# Isolation.net
KiCad netlist of a schematic drawn in Altium Designer
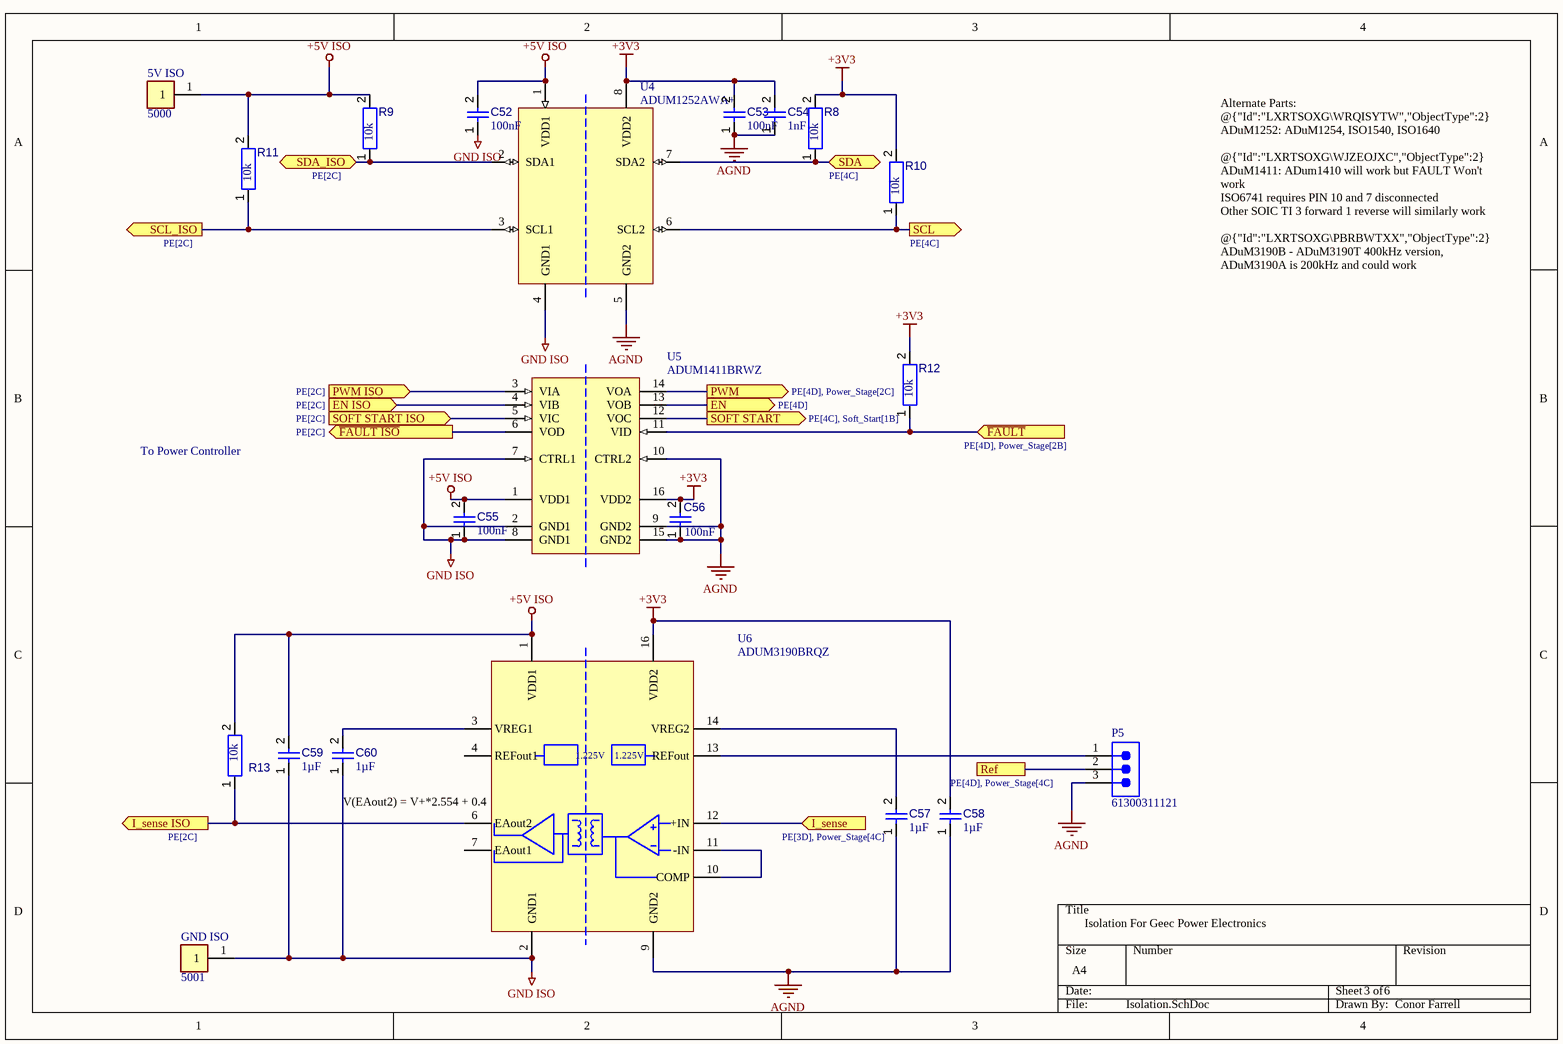
[diagram p0: Isolation.SchDoc]

(export (version "E")
  (design (tool "Eeschema 10.0.6"))
  (components
    (comp (ref "5V ISO")
      (value "5000")
      (footprint "FP-5000-MFG")
      (description "Cable Wrap, 1/2 Inch, Polyethylene, Natural, 50 Ft, Spirap Series")
      (libsource (lib "University of Galway") (part "1e4615820a309e3ce90f9e6d957b7fa"))
    )
    (comp (ref "C52")
      (value "100nF")
      (footprint "CAPC3216X06N")
      (description "Ceramic Capacitor, Multilayer, Ceramic, 200V, 10% +Tol, 10% -Tol, X7R, 15% TC, 0.01uF, 1206")
      (fields (field (name "TOLERANCE") "10%") (field (name "Comment") "C1206C104K1RACTU"))
      (libsource (lib "University of Galway") (part "CAP-NP-2"))
    )
    (comp (ref "C53")
      (value "100nF")
      (footprint "CAPC3216X06N")
      (description "Ceramic Capacitor, Multilayer, Ceramic, 200V, 10% +Tol, 10% -Tol, X7R, 15% TC, 0.01uF, 1206")
      (fields (field (name "TOLERANCE") "10%") (field (name "Comment") "C1206C104K1RACTU"))
      (libsource (lib "University of Galway") (part "CAP-NP-2"))
    )
    (comp (ref "C54")
      (value "1nF")
      (footprint "FP-CL31-IPC_A")
      (fields (field (name "TOLERANCE") "10%") (field (name "Comment") "CL31B102KGFNNNE"))
      (libsource (lib "University of Galway") (part "CAP-NP-2"))
    )
    (comp (ref "C55")
      (value "100nF")
      (footprint "CAPC3216X06N")
      (description "Ceramic Capacitor, Multilayer, Ceramic, 200V, 10% +Tol, 10% -Tol, X7R, 15% TC, 0.01uF, 1206")
      (fields (field (name "TOLERANCE") "10%") (field (name "Comment") "C1206C104K1RACTU"))
      (libsource (lib "University of Galway") (part "CAP-NP-2"))
    )
    (comp (ref "C56")
      (value "100nF")
      (footprint "CAPC3216X06N")
      (description "Ceramic Capacitor, Multilayer, Ceramic, 200V, 10% +Tol, 10% -Tol, X7R, 15% TC, 0.01uF, 1206")
      (fields (field (name "TOLERANCE") "10%") (field (name "Comment") "C1206C104K1RACTU"))
      (libsource (lib "University of Galway") (part "CAP-NP-2"))
    )
    (comp (ref "C57")
      (value "1µF")
      (footprint "CAPC3216X180X20ML20")
      (fields (field (name "TOLERANCE") "10%") (field (name "Comment") "CL31B105KBHNNNE"))
      (libsource (lib "University of Galway") (part "CAP-NP-2"))
    )
    (comp (ref "C58")
      (value "1µF")
      (footprint "CAPC3216X180X20ML20")
      (fields (field (name "TOLERANCE") "10%") (field (name "Comment") "CL31B105KBHNNNE"))
      (libsource (lib "University of Galway") (part "CAP-NP-2"))
    )
    (comp (ref "C59")
      (value "1µF")
      (footprint "CAPC3216X180X20ML20")
      (fields (field (name "TOLERANCE") "10%") (field (name "Comment") "CL31B105KBHNNNE"))
      (libsource (lib "University of Galway") (part "CAP-NP-2"))
    )
    (comp (ref "C60")
      (value "1µF")
      (footprint "CAPC3216X180X20ML20")
      (fields (field (name "TOLERANCE") "10%") (field (name "Comment") "CL31B105KBHNNNE"))
      (libsource (lib "University of Galway") (part "CAP-NP-2"))
    )
    (comp (ref "GND ISO")
      (value "5001")
      (footprint "FP-5001-MFG")
      (description "Test Point, Mini, Thm, Pc, .300 L, .100 Od, Heat Resistant Nylon 46, Black")
      (libsource (lib "University of Galway") (part "1e4615820a309e3ce90f9e6d957b7fa"))
    )
    (comp (ref "P5")
      (value "61300311121")
      (footprint "61300311121")
      (description "WR-PHD Pin Header, THT, Vertical, pitch 2.54mm, 1 Row, 3P")
      (fields (field (name "MANUFACTURER") "Wurth Elektronik"))
      (libsource (lib "University of Galway") (part "62000311121"))
    )
    (comp (ref "R8")
      (value "10k")
      (footprint "RESC3216X60X45ML15T20")
      (description "Res Thick Film 1206 10K Ohm 1% 0.25W(1/4W) ±100ppm/C Pad SMD T/R")
      (fields (field (name "Comment") "1206W4F1002T5E"))
      (libsource (lib "University of Galway") (part "RES-2"))
    )
    (comp (ref "R9")
      (value "10k")
      (footprint "RESC3216X60X45ML15T20")
      (description "Res Thick Film 1206 10K Ohm 1% 0.25W(1/4W) ±100ppm/C Pad SMD T/R")
      (fields (field (name "Comment") "1206W4F1002T5E"))
      (libsource (lib "University of Galway") (part "RES-2"))
    )
    (comp (ref "R10")
      (value "10k")
      (footprint "RESC3216X60X45ML15T20")
      (description "Res Thick Film 1206 10K Ohm 1% 0.25W(1/4W) ±100ppm/C Pad SMD T/R")
      (fields (field (name "Comment") "1206W4F1002T5E"))
      (libsource (lib "University of Galway") (part "RES-2"))
    )
    (comp (ref "R11")
      (value "10k")
      (footprint "RESC3216X60X45ML15T20")
      (description "Res Thick Film 1206 10K Ohm 1% 0.25W(1/4W) ±100ppm/C Pad SMD T/R")
      (fields (field (name "Comment") "1206W4F1002T5E"))
      (libsource (lib "University of Galway") (part "RES-2"))
    )
    (comp (ref "R12")
      (value "10k")
      (footprint "RESC3216X60X45ML15T20")
      (description "Res Thick Film 1206 10K Ohm 1% 0.25W(1/4W) ±100ppm/C Pad SMD T/R")
      (fields (field (name "Comment") "1206W4F1002T5E"))
      (libsource (lib "University of Galway") (part "RES-2"))
    )
    (comp (ref "R13")
      (value "10k")
      (footprint "RESC3216X60X45ML15T20")
      (description "Res Thick Film 1206 10K Ohm 1% 0.25W(1/4W) ±100ppm/C Pad SMD T/R")
      (fields (field (name "Comment") "1206W4F1002T5E"))
      (libsource (lib "University of Galway") (part "RES-2"))
    )
    (comp (ref "U4")
      (value "ADUM1252AWA+")
      (footprint "SOIC127P1030X265-8N")
      (description "Ultra-Low Power, Bidirectional I2C Isolator with Extended VDD, Idle-Bus Hot-Swap and Low VOL")
      (libsource (lib "University of Galway") (part "ADUM1252AWA+-Symbol-1"))
    )
    (comp (ref "U5")
      (value "ADUM1411BRWZ")
      (footprint "ADI-RW-16_M")
      (description "Digital Isolator CMOS 4-CH 10Mbps 16-Pin SOIC W Tube / DGTL ISO 3.75KV GEN PURP 16SOIC")
      (libsource (lib "University of Galway") (part "ADI-ADUM1411-RW-16"))
    )
    (comp (ref "U6")
      (value "ADUM3190BRQZ")
      (footprint "SOP64P600X175-16N")
      (description "High Stability Isolated Error Amplifier")
      (libsource (lib "University of Galway") (part "ADUM3190BRQZ-Symbol-1"))
    )
  )
  (nets
    (net (code "1") (name "+3V3") (class "Default")
      (node (ref "C53") (pin "2") (pinfunction "2_2") (pintype "passive"))
      (node (ref "C54") (pin "2") (pinfunction "2_2") (pintype "passive"))
      (node (ref "C56") (pin "2") (pinfunction "2_2") (pintype "passive"))
      (node (ref "C58") (pin "2") (pinfunction "2_2") (pintype "passive"))
      (node (ref "R10") (pin "2") (pinfunction "2_2") (pintype "passive"))
      (node (ref "R12") (pin "2") (pinfunction "2_2") (pintype "passive"))
      (node (ref "R8") (pin "2") (pinfunction "2_2") (pintype "passive"))
      (node (ref "U4") (pin "8") (pinfunction "VDD2_8") (pintype "passive"))
      (node (ref "U5") (pin "16") (pinfunction "VDD2_16") (pintype "power_in"))
      (node (ref "U6") (pin "16") (pinfunction "VDD2_16") (pintype "passive"))
    )
    (net (code "2") (name "+5V ISO") (class "Default")
      (node (ref "5V ISO") (pin "1") (pinfunction "1_1") (pintype "passive"))
      (node (ref "C52") (pin "2") (pinfunction "2_2") (pintype "passive"))
      (node (ref "C55") (pin "2") (pinfunction "2_2") (pintype "passive"))
      (node (ref "C59") (pin "2") (pinfunction "2_2") (pintype "passive"))
      (node (ref "R11") (pin "2") (pinfunction "2_2") (pintype "passive"))
      (node (ref "R13") (pin "2") (pinfunction "2_2") (pintype "passive"))
      (node (ref "R9") (pin "2") (pinfunction "2_2") (pintype "passive"))
      (node (ref "U4") (pin "1") (pinfunction "VDD1_1") (pintype "input"))
      (node (ref "U5") (pin "1") (pinfunction "VDD1_1") (pintype "power_in"))
      (node (ref "U6") (pin "1") (pinfunction "VDD1_1") (pintype "passive"))
    )
    (net (code "3") (name "/EN") (class "Default")
      (node (ref "U5") (pin "13") (pinfunction "VOB_13") (pintype "tri_state"))
    )
    (net (code "4") (name "/EN ISO") (class "Default")
      (node (ref "U5") (pin "4") (pinfunction "VIB_4") (pintype "input"))
    )
    (net (code "5") (name "/I_sense") (class "Default")
      (node (ref "U6") (pin "12") (pinfunction "+IN_12") (pintype "passive"))
    )
    (net (code "6") (name "/I_sense ISO") (class "Default")
      (node (ref "R13") (pin "1") (pinfunction "1_1") (pintype "passive"))
      (node (ref "U6") (pin "6") (pinfunction "EAout2_6") (pintype "passive"))
    )
    (net (code "7") (name "/PWM") (class "Default")
      (node (ref "U5") (pin "14") (pinfunction "VOA_14") (pintype "tri_state"))
    )
    (net (code "8") (name "/PWM ISO") (class "Default")
      (node (ref "U5") (pin "3") (pinfunction "VIA_3") (pintype "input"))
    )
    (net (code "9") (name "/Ref") (class "Default")
      (node (ref "P5") (pin "2") (pinfunction "2_2") (pintype "passive"))
    )
    (net (code "10") (name "/SCL") (class "Default")
      (node (ref "R10") (pin "1") (pinfunction "1_1") (pintype "passive"))
      (node (ref "U4") (pin "6") (pinfunction "SCL2_6") (pintype "bidirectional"))
    )
    (net (code "11") (name "/SCL_ISO") (class "Default")
      (node (ref "R11") (pin "1") (pinfunction "1_1") (pintype "passive"))
      (node (ref "U4") (pin "3") (pinfunction "SCL1_3") (pintype "bidirectional"))
    )
    (net (code "12") (name "/SDA") (class "Default")
      (node (ref "R8") (pin "1") (pinfunction "1_1") (pintype "passive"))
      (node (ref "U4") (pin "7") (pinfunction "SDA2_7") (pintype "bidirectional"))
    )
    (net (code "13") (name "/SDA_ISO") (class "Default")
      (node (ref "R9") (pin "1") (pinfunction "1_1") (pintype "passive"))
      (node (ref "U4") (pin "2") (pinfunction "SDA1_2") (pintype "bidirectional"))
    )
    (net (code "14") (name "/SOFT START") (class "Default")
      (node (ref "U5") (pin "12") (pinfunction "VOC_12") (pintype "tri_state"))
    )
    (net (code "15") (name "/SOFT START ISO") (class "Default")
      (node (ref "U5") (pin "5") (pinfunction "VIC_5") (pintype "input"))
    )
    (net (code "16") (name "/~{FAULT ISO}") (class "Default")
      (node (ref "U5") (pin "6") (pinfunction "VOD_6") (pintype "tri_state"))
    )
    (net (code "17") (name "/~{FAULT}") (class "Default")
      (node (ref "R12") (pin "1") (pinfunction "1_1") (pintype "passive"))
      (node (ref "U5") (pin "11") (pinfunction "VID_11") (pintype "input"))
    )
    (net (code "18") (name "AGND") (class "Default")
      (node (ref "C53") (pin "1") (pinfunction "1_1") (pintype "passive"))
      (node (ref "C54") (pin "1") (pinfunction "1_1") (pintype "passive"))
      (node (ref "C56") (pin "1") (pinfunction "1_1") (pintype "passive"))
      (node (ref "C57") (pin "1") (pinfunction "1_1") (pintype "passive"))
      (node (ref "C58") (pin "1") (pinfunction "1_1") (pintype "passive"))
      (node (ref "P5") (pin "3") (pinfunction "3_3") (pintype "passive"))
      (node (ref "U4") (pin "5") (pinfunction "GND2_5") (pintype "passive"))
      (node (ref "U5") (pin "10") (pinfunction "CTRL2_10") (pintype "input"))
      (node (ref "U5") (pin "15") (pinfunction "GND2_15") (pintype "power_in"))
      (node (ref "U5") (pin "9") (pinfunction "GND2_9") (pintype "power_in"))
      (node (ref "U6") (pin "9") (pinfunction "GND2_9") (pintype "passive"))
    )
    (net (code "19") (name "GND ISO") (class "Default")
      (node (ref "C52") (pin "1") (pinfunction "1_1") (pintype "passive"))
      (node (ref "C55") (pin "1") (pinfunction "1_1") (pintype "passive"))
      (node (ref "C59") (pin "1") (pinfunction "1_1") (pintype "passive"))
      (node (ref "C60") (pin "1") (pinfunction "1_1") (pintype "passive"))
      (node (ref "GND ISO") (pin "1") (pinfunction "1_1") (pintype "passive"))
      (node (ref "U4") (pin "4") (pinfunction "GND1_4") (pintype "passive"))
      (node (ref "U5") (pin "2") (pinfunction "GND1_2") (pintype "power_in"))
      (node (ref "U5") (pin "7") (pinfunction "CTRL1_7") (pintype "input"))
      (node (ref "U5") (pin "8") (pinfunction "GND1_8") (pintype "power_in"))
      (node (ref "U6") (pin "2") (pinfunction "GND1_2") (pintype "passive"))
    )
    (net (code "20") (name "Net-(U6--IN)") (class "Default")
      (node (ref "U6") (pin "10") (pinfunction "COMP_10") (pintype "passive"))
      (node (ref "U6") (pin "11") (pinfunction "-IN_11") (pintype "passive"))
    )
    (net (code "21") (name "Net-(U6-REFout)") (class "Default")
      (node (ref "P5") (pin "1") (pinfunction "1_1") (pintype "passive"))
      (node (ref "U6") (pin "13") (pinfunction "REFout_13") (pintype "power_in"))
    )
    (net (code "22") (name "Net-(U6-VREG1)") (class "Default")
      (node (ref "C60") (pin "2") (pinfunction "2_2") (pintype "passive"))
      (node (ref "U6") (pin "3") (pinfunction "VREG1_3") (pintype "passive"))
    )
    (net (code "23") (name "Net-(U6-VREG2)") (class "Default")
      (node (ref "C57") (pin "2") (pinfunction "2_2") (pintype "passive"))
      (node (ref "U6") (pin "14") (pinfunction "VREG2_14") (pintype "passive"))
    )
    (net (code "24") (name "unconnected-(U6-EAout1-Pad7)") (class "Default")
      (node (ref "U6") (pin "7") (pinfunction "EAout1_7") (pintype "passive"))
    )
    (net (code "25") (name "unconnected-(U6-REFout1-Pad4)") (class "Default")
      (node (ref "U6") (pin "4") (pinfunction "REFout1_4") (pintype "passive"))
    )
  )
)
